# HW2.net
KiCad netlist of a schematic drawn in EAGLE
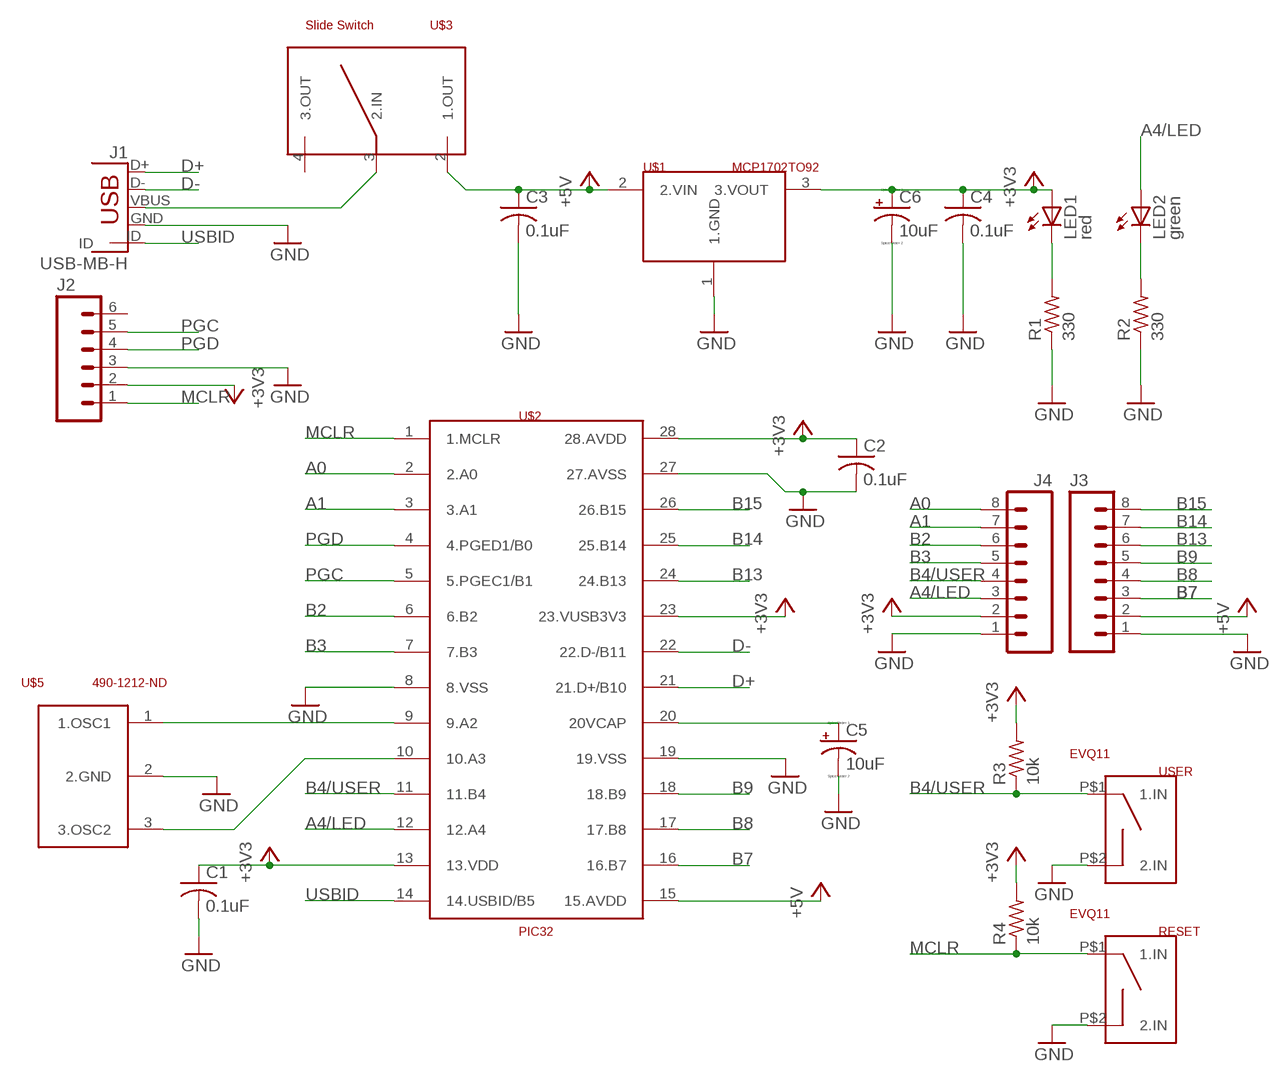
[diagram p0: schematic, sheet 1]

(export (version "E")
  (design (tool "Eeschema 10.0.6"))
  (components
    (comp (ref "C1")
      (value "0.1uF")
      (footprint "eagle-import:C025-024X044")
      (libsource (lib "eagle-import") (part "C-US025-024X044"))
    )
    (comp (ref "C2")
      (value "0.1uF")
      (footprint "eagle-import:C025-024X044")
      (libsource (lib "eagle-import") (part "C-US025-024X044"))
    )
    (comp (ref "C3")
      (value "0.1uF")
      (footprint "eagle-import:C025-024X044")
      (libsource (lib "eagle-import") (part "C-US025-024X044"))
    )
    (comp (ref "C4")
      (value "0.1uF")
      (footprint "eagle-import:C025-024X044")
      (libsource (lib "eagle-import") (part "C-US025-024X044"))
    )
    (comp (ref "C5")
      (value "10uF")
      (footprint "eagle-import:B45181A")
      (libsource (lib "eagle-import") (part "CPOL-USB45181A"))
    )
    (comp (ref "C6")
      (value "10uF")
      (footprint "eagle-import:B45181A")
      (libsource (lib "eagle-import") (part "CPOL-USB45181A"))
    )
    (comp (ref "J1")
      (value "USB-MB-H")
      (footprint "eagle-import:USB-MB-H")
      (libsource (lib "eagle-import") (part "USB-MB-H"))
    )
    (comp (ref "J2")
      (value "M06SILK_FEMALE_PTH")
      (footprint "eagle-import:1X06")
      (libsource (lib "eagle-import") (part "M06SILK_FEMALE_PTH"))
    )
    (comp (ref "J3")
      (value "M08SILK_FEMALE_PTH")
      (footprint "eagle-import:1X08")
      (libsource (lib "eagle-import") (part "M08SILK_FEMALE_PTH"))
    )
    (comp (ref "J4")
      (value "M08SILK_FEMALE_PTH")
      (footprint "eagle-import:1X08")
      (libsource (lib "eagle-import") (part "M08SILK_FEMALE_PTH"))
    )
    (comp (ref "LED1")
      (value "red")
      (footprint "eagle-import:LED3MM")
      (libsource (lib "eagle-import") (part "LED3MM"))
    )
    (comp (ref "LED2")
      (value "green")
      (footprint "eagle-import:LED3MM")
      (libsource (lib "eagle-import") (part "LED3MM"))
    )
    (comp (ref "R1")
      (value "330")
      (footprint "eagle-import:0204_7")
      (libsource (lib "eagle-import") (part "R-US_0204/7"))
    )
    (comp (ref "R2")
      (value "330")
      (footprint "eagle-import:0204_7")
      (libsource (lib "eagle-import") (part "R-US_0204/7"))
    )
    (comp (ref "R3")
      (value "10k")
      (footprint "eagle-import:0204_7")
      (libsource (lib "eagle-import") (part "R-US_0204/7"))
    )
    (comp (ref "R4")
      (value "10k")
      (footprint "eagle-import:0204_7")
      (libsource (lib "eagle-import") (part "R-US_0204/7"))
    )
    (comp (ref "RESET")
      (value "EVQ11")
      (footprint "eagle-import:1X02_BIG")
      (libsource (lib "eagle-import") (part "EVQ11"))
    )
    (comp (ref "U$1")
      (value "MCP1702TO92")
      (footprint "eagle-import:TO92")
      (libsource (lib "eagle-import") (part "MCP1702TO92"))
    )
    (comp (ref "U$2")
      (value "PIC32")
      (footprint "eagle-import:DIL28-3")
      (libsource (lib "eagle-import") (part "PIC32"))
    )
    (comp (ref "U$3")
      (value "A107673-ND")
      (footprint "eagle-import:1X05_NO_SILK")
      (libsource (lib "eagle-import") (part "A107673-ND"))
    )
    (comp (ref "U$5")
      (value "490-1212-ND")
      (footprint "eagle-import:1X03_NO_SILK")
      (libsource (lib "eagle-import") (part "490-1212-ND"))
    )
    (comp (ref "USER")
      (value "EVQ11")
      (footprint "eagle-import:1X02_BIG")
      (libsource (lib "eagle-import") (part "EVQ11"))
    )
  )
  (nets
    (net (code "1") (name "+3V3") (class "Default")
      (node (ref "C1") (pin "1") (pinfunction "1_1") (pintype "passive"))
      (node (ref "C2") (pin "1") (pinfunction "1_1") (pintype "passive"))
      (node (ref "C4") (pin "1") (pinfunction "1_1") (pintype "passive"))
      (node (ref "C6") (pin "+") (pinfunction "+_+") (pintype "passive"))
      (node (ref "J2") (pin "2") (pinfunction "2_2") (pintype "passive"))
      (node (ref "J4") (pin "2") (pinfunction "2_2") (pintype "passive"))
      (node (ref "LED1") (pin "A") (pinfunction "A_A") (pintype "passive"))
      (node (ref "R3") (pin "2") (pinfunction "2_2") (pintype "passive"))
      (node (ref "R4") (pin "2") (pinfunction "2_2") (pintype "passive"))
      (node (ref "U$1") (pin "3") (pinfunction "3.VOUT_3") (pintype "bidirectional"))
      (node (ref "U$2") (pin "13") (pinfunction "13.VDD_13") (pintype "bidirectional"))
      (node (ref "U$2") (pin "23") (pinfunction "23.VUSB3V3_23") (pintype "bidirectional"))
      (node (ref "U$2") (pin "28") (pinfunction "28.AVDD_28") (pintype "bidirectional"))
    )
    (net (code "2") (name "+5V") (class "Default")
      (node (ref "C3") (pin "1") (pinfunction "1_1") (pintype "passive"))
      (node (ref "J3") (pin "2") (pinfunction "2_2") (pintype "passive"))
      (node (ref "U$1") (pin "2") (pinfunction "2.VIN_2") (pintype "bidirectional"))
      (node (ref "U$2") (pin "15") (pinfunction "15.AVDD_15") (pintype "bidirectional"))
      (node (ref "U$3") (pin "2") (pinfunction "1.OUT_2") (pintype "bidirectional"))
    )
    (net (code "3") (name "/A0") (class "Default")
      (node (ref "J4") (pin "8") (pinfunction "8_8") (pintype "passive"))
      (node (ref "U$2") (pin "2") (pinfunction "2.A0_2") (pintype "bidirectional"))
    )
    (net (code "4") (name "/A1") (class "Default")
      (node (ref "J4") (pin "7") (pinfunction "7_7") (pintype "passive"))
      (node (ref "U$2") (pin "3") (pinfunction "3.A1_3") (pintype "bidirectional"))
    )
    (net (code "5") (name "/A4{slash}LED") (class "Default")
      (node (ref "J4") (pin "3") (pinfunction "3_3") (pintype "passive"))
      (node (ref "LED2") (pin "A") (pinfunction "A_A") (pintype "passive"))
      (node (ref "U$2") (pin "12") (pinfunction "12.A4_12") (pintype "bidirectional"))
    )
    (net (code "6") (name "/B2") (class "Default")
      (node (ref "J4") (pin "6") (pinfunction "6_6") (pintype "passive"))
      (node (ref "U$2") (pin "6") (pinfunction "6.B2_6") (pintype "bidirectional"))
    )
    (net (code "7") (name "/B3") (class "Default")
      (node (ref "J4") (pin "5") (pinfunction "5_5") (pintype "passive"))
      (node (ref "U$2") (pin "7") (pinfunction "7.B3_7") (pintype "bidirectional"))
    )
    (net (code "8") (name "/B4{slash}USER") (class "Default")
      (node (ref "J4") (pin "4") (pinfunction "4_4") (pintype "passive"))
      (node (ref "R3") (pin "1") (pinfunction "1_1") (pintype "passive"))
      (node (ref "U$2") (pin "11") (pinfunction "11.B4_11") (pintype "bidirectional"))
      (node (ref "USER") (pin "P$1") (pinfunction "1.IN_P$1") (pintype "bidirectional"))
    )
    (net (code "9") (name "/B7") (class "Default")
      (node (ref "J3") (pin "3") (pinfunction "3_3") (pintype "passive"))
      (node (ref "U$2") (pin "16") (pinfunction "16.B7_16") (pintype "bidirectional"))
    )
    (net (code "10") (name "/B8") (class "Default")
      (node (ref "J3") (pin "4") (pinfunction "4_4") (pintype "passive"))
      (node (ref "U$2") (pin "17") (pinfunction "17.B8_17") (pintype "bidirectional"))
    )
    (net (code "11") (name "/B9") (class "Default")
      (node (ref "J3") (pin "5") (pinfunction "5_5") (pintype "passive"))
      (node (ref "U$2") (pin "18") (pinfunction "18.B9_18") (pintype "bidirectional"))
    )
    (net (code "12") (name "/B13") (class "Default")
      (node (ref "J3") (pin "6") (pinfunction "6_6") (pintype "passive"))
      (node (ref "U$2") (pin "24") (pinfunction "24.B13_24") (pintype "bidirectional"))
    )
    (net (code "13") (name "/B14") (class "Default")
      (node (ref "J3") (pin "7") (pinfunction "7_7") (pintype "passive"))
      (node (ref "U$2") (pin "25") (pinfunction "25.B14_25") (pintype "bidirectional"))
    )
    (net (code "14") (name "/B15") (class "Default")
      (node (ref "J3") (pin "8") (pinfunction "8_8") (pintype "passive"))
      (node (ref "U$2") (pin "26") (pinfunction "26.B15_26") (pintype "bidirectional"))
    )
    (net (code "15") (name "/D+") (class "Default")
      (node (ref "J1") (pin "D+") (pinfunction "D+_D+") (pintype "bidirectional"))
      (node (ref "U$2") (pin "21") (pinfunction "21.D+/B10_21") (pintype "bidirectional"))
    )
    (net (code "16") (name "/D-") (class "Default")
      (node (ref "J1") (pin "D-") (pinfunction "D-_D-") (pintype "bidirectional"))
      (node (ref "U$2") (pin "22") (pinfunction "22.D-/B11_22") (pintype "bidirectional"))
    )
    (net (code "17") (name "/MCLR") (class "Default")
      (node (ref "J2") (pin "1") (pinfunction "1_1") (pintype "passive"))
      (node (ref "R4") (pin "1") (pinfunction "1_1") (pintype "passive"))
      (node (ref "RESET") (pin "P$1") (pinfunction "1.IN_P$1") (pintype "bidirectional"))
      (node (ref "U$2") (pin "1") (pinfunction "1.MCLR_1") (pintype "bidirectional"))
    )
    (net (code "18") (name "/PGC") (class "Default")
      (node (ref "J2") (pin "5") (pinfunction "5_5") (pintype "passive"))
      (node (ref "U$2") (pin "5") (pinfunction "5.PGEC1/B1_5") (pintype "bidirectional"))
    )
    (net (code "19") (name "/PGD") (class "Default")
      (node (ref "J2") (pin "4") (pinfunction "4_4") (pintype "passive"))
      (node (ref "U$2") (pin "4") (pinfunction "4.PGED1/B0_4") (pintype "bidirectional"))
    )
    (net (code "20") (name "/USBID") (class "Default")
      (node (ref "J1") (pin "ID") (pinfunction "ID_ID") (pintype "bidirectional"))
      (node (ref "U$2") (pin "14") (pinfunction "14.USBID/B5_14") (pintype "bidirectional"))
    )
    (net (code "21") (name "GND") (class "Default")
      (node (ref "C1") (pin "2") (pinfunction "2_2") (pintype "passive"))
      (node (ref "C2") (pin "2") (pinfunction "2_2") (pintype "passive"))
      (node (ref "C3") (pin "2") (pinfunction "2_2") (pintype "passive"))
      (node (ref "C4") (pin "2") (pinfunction "2_2") (pintype "passive"))
      (node (ref "C5") (pin "-") (pinfunction "-_-") (pintype "passive"))
      (node (ref "C6") (pin "-") (pinfunction "-_-") (pintype "passive"))
      (node (ref "J1") (pin "GND") (pinfunction "GND_GND") (pintype "bidirectional"))
      (node (ref "J2") (pin "3") (pinfunction "3_3") (pintype "passive"))
      (node (ref "J3") (pin "1") (pinfunction "1_1") (pintype "passive"))
      (node (ref "J4") (pin "1") (pinfunction "1_1") (pintype "passive"))
      (node (ref "R1") (pin "1") (pinfunction "1_1") (pintype "passive"))
      (node (ref "R2") (pin "1") (pinfunction "1_1") (pintype "passive"))
      (node (ref "RESET") (pin "P$2") (pinfunction "2.IN_P$2") (pintype "bidirectional"))
      (node (ref "U$1") (pin "1") (pinfunction "1.GND_1") (pintype "bidirectional"))
      (node (ref "U$2") (pin "19") (pinfunction "19.VSS_19") (pintype "bidirectional"))
      (node (ref "U$2") (pin "27") (pinfunction "27.AVSS_27") (pintype "bidirectional"))
      (node (ref "U$2") (pin "8") (pinfunction "8.VSS_8") (pintype "bidirectional"))
      (node (ref "U$5") (pin "2") (pinfunction "2.GND_2") (pintype "bidirectional"))
      (node (ref "USER") (pin "P$2") (pinfunction "2.IN_P$2") (pintype "bidirectional"))
    )
    (net (code "22") (name "Net-(LED1-C)") (class "Default")
      (node (ref "LED1") (pin "K") (pinfunction "C_K") (pintype "passive"))
      (node (ref "R1") (pin "2") (pinfunction "2_2") (pintype "passive"))
    )
    (net (code "23") (name "Net-(LED2-C)") (class "Default")
      (node (ref "LED2") (pin "K") (pinfunction "C_K") (pintype "passive"))
      (node (ref "R2") (pin "2") (pinfunction "2_2") (pintype "passive"))
    )
    (net (code "24") (name "Net-(U$2-9.A2)") (class "Default")
      (node (ref "U$2") (pin "9") (pinfunction "9.A2_9") (pintype "bidirectional"))
      (node (ref "U$5") (pin "1") (pinfunction "1.OSC1_1") (pintype "bidirectional"))
    )
    (net (code "25") (name "Net-(U$2-10.A3)") (class "Default")
      (node (ref "U$2") (pin "10") (pinfunction "10.A3_10") (pintype "bidirectional"))
      (node (ref "U$5") (pin "3") (pinfunction "3.OSC2_3") (pintype "bidirectional"))
    )
    (net (code "26") (name "Net-(U$2-20VCAP)") (class "Default")
      (node (ref "C5") (pin "+") (pinfunction "+_+") (pintype "passive"))
      (node (ref "U$2") (pin "20") (pinfunction "20VCAP_20") (pintype "bidirectional"))
    )
    (net (code "27") (name "Net-(U$3-2.IN)") (class "Default")
      (node (ref "J1") (pin "VBUS") (pinfunction "VBUS_VBUS") (pintype "bidirectional"))
      (node (ref "U$3") (pin "3") (pinfunction "2.IN_3") (pintype "bidirectional"))
    )
    (net (code "28") (name "unconnected-(J2-Pad6)") (class "Default")
      (node (ref "J2") (pin "6") (pinfunction "6_6") (pintype "passive"))
    )
    (net (code "29") (name "unconnected-(U$3-3.OUT-Pad4)") (class "Default")
      (node (ref "U$3") (pin "4") (pinfunction "3.OUT_4") (pintype "bidirectional"))
    )
  )
)
